# BumpSensors.net
KiCad netlist of a schematic drawn in Altium Designer
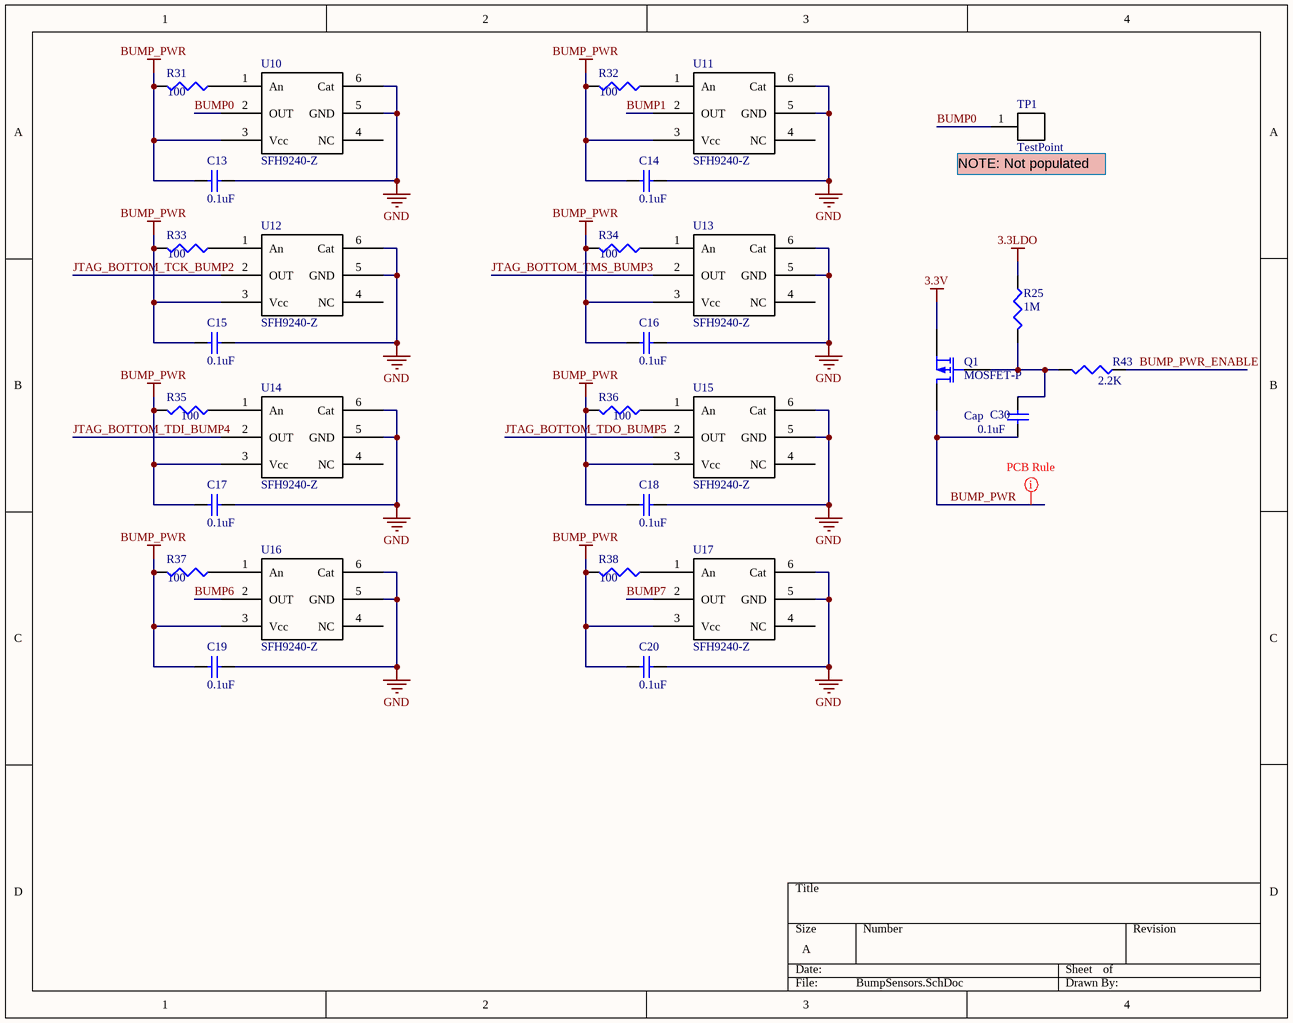
[diagram p0: BumpSensors.SchDoc]

(export (version "E")
  (design (tool "Eeschema 10.0.6"))
  (components
    (comp (ref "C13")
      (value "0.1uF")
      (footprint "CAPC1005L")
      (description "Capacitor (Semiconductor SIM Model)")
      (fields
        (field (name "PART NUMBER") "GRM155R71C104KA88D")
        (field (name "MANUFACTURER") "Murata")
        (field (name "PUBLISHER") "Altium Limited")
      )
      (libsource (lib "Miscellaneous Devices") (part "Cap Semi"))
    )
    (comp (ref "C14")
      (value "0.1uF")
      (footprint "CAPC1005L")
      (description "Capacitor (Semiconductor SIM Model)")
      (fields
        (field (name "PART NUMBER") "GRM155R71C104KA88D")
        (field (name "MANUFACTURER") "Murata")
        (field (name "PUBLISHER") "Altium Limited")
      )
      (libsource (lib "Miscellaneous Devices") (part "Cap Semi"))
    )
    (comp (ref "C15")
      (value "0.1uF")
      (footprint "CAPC1005L")
      (description "Capacitor (Semiconductor SIM Model)")
      (fields
        (field (name "PART NUMBER") "GRM155R71C104KA88D")
        (field (name "MANUFACTURER") "Murata")
        (field (name "PUBLISHER") "Altium Limited")
      )
      (libsource (lib "Miscellaneous Devices") (part "Cap Semi"))
    )
    (comp (ref "C16")
      (value "0.1uF")
      (footprint "CAPC1005L")
      (description "Capacitor (Semiconductor SIM Model)")
      (fields
        (field (name "PART NUMBER") "GRM155R71C104KA88D")
        (field (name "MANUFACTURER") "Murata")
        (field (name "PUBLISHER") "Altium Limited")
      )
      (libsource (lib "Miscellaneous Devices") (part "Cap Semi"))
    )
    (comp (ref "C17")
      (value "0.1uF")
      (footprint "CAPC1005L")
      (description "Capacitor (Semiconductor SIM Model)")
      (fields
        (field (name "PART NUMBER") "GRM155R71C104KA88D")
        (field (name "MANUFACTURER") "Murata")
        (field (name "PUBLISHER") "Altium Limited")
      )
      (libsource (lib "Miscellaneous Devices") (part "Cap Semi"))
    )
    (comp (ref "C18")
      (value "0.1uF")
      (footprint "CAPC1005L")
      (description "Capacitor (Semiconductor SIM Model)")
      (fields
        (field (name "PART NUMBER") "GRM155R71C104KA88D")
        (field (name "MANUFACTURER") "Murata")
        (field (name "PUBLISHER") "Altium Limited")
      )
      (libsource (lib "Miscellaneous Devices") (part "Cap Semi"))
    )
    (comp (ref "C19")
      (value "0.1uF")
      (footprint "CAPC1005L")
      (description "Capacitor (Semiconductor SIM Model)")
      (fields
        (field (name "PART NUMBER") "GRM155R71C104KA88D")
        (field (name "MANUFACTURER") "Murata")
        (field (name "PUBLISHER") "Altium Limited")
      )
      (libsource (lib "Miscellaneous Devices") (part "Cap Semi"))
    )
    (comp (ref "C20")
      (value "0.1uF")
      (footprint "CAPC1005L")
      (description "Capacitor (Semiconductor SIM Model)")
      (fields
        (field (name "PART NUMBER") "GRM155R71C104KA88D")
        (field (name "MANUFACTURER") "Murata")
        (field (name "PUBLISHER") "Altium Limited")
      )
      (libsource (lib "Miscellaneous Devices") (part "Cap Semi"))
    )
    (comp (ref "C30")
      (value "Cap")
      (footprint "CAPC1005L")
      (description "Capacitor")
      (fields
        (field (name "ALTIUM_VALUE") "0.1uF")
        (field (name "PART NUMBER") "GRM155R71C104KA88D")
        (field (name "MANUFACTURER") "Murata")
        (field (name "PUBLISHER") "Altium Limited")
      )
      (libsource (lib "mrone") (part "Cap"))
    )
    (comp (ref "Q1")
      (value "MOSFET-P")
      (footprint "SOT-23")
      (description "P-Channel MOSFET")
      (fields
        (field (name "PART NUMBER") "DMG2301U-7")
        (field (name "MANUFACTURER") "Diodes")
        (field (name "PUBLISHER") "Altium Limited")
      )
      (libsource (lib "mrone") (part "MOSFET-P"))
    )
    (comp (ref "R25")
      (value "1M")
      (footprint "J1-0603")
      (description "Resistor")
      (fields
        (field (name "PART NUMBER") "ERJ-3GEY-J105V")
        (field (name "MANUFACTURER") "Panasonic")
        (field (name "PUBLISHER") "Altium Limited")
      )
      (libsource (lib "Miscellaneous Devices") (part "Res3"))
    )
    (comp (ref "R31")
      (value "100")
      (footprint "RESC1608L")
      (description "Resistor")
      (fields
        (field (name "PART NUMBER") "ERJ-3GEYJ101V")
        (field (name "MANUFACTURER") "Panasonic")
        (field (name "PUBLISHER") "Altium Limited")
      )
      (libsource (lib "Miscellaneous Devices") (part "Res3"))
    )
    (comp (ref "R32")
      (value "100")
      (footprint "RESC1608L")
      (description "Resistor")
      (fields
        (field (name "PART NUMBER") "ERJ-3GEYJ101V")
        (field (name "MANUFACTURER") "Panasonic")
        (field (name "PUBLISHER") "Altium Limited")
      )
      (libsource (lib "Miscellaneous Devices") (part "Res3"))
    )
    (comp (ref "R33")
      (value "100")
      (footprint "RESC1608L")
      (description "Resistor")
      (fields
        (field (name "PART NUMBER") "ERJ-3GEYJ101V")
        (field (name "MANUFACTURER") "Panasonic")
        (field (name "PUBLISHER") "Altium Limited")
      )
      (libsource (lib "Miscellaneous Devices") (part "Res3"))
    )
    (comp (ref "R34")
      (value "100")
      (footprint "RESC1608L")
      (description "Resistor")
      (fields
        (field (name "PART NUMBER") "ERJ-3GEYJ101V")
        (field (name "MANUFACTURER") "Panasonic")
        (field (name "PUBLISHER") "Altium Limited")
      )
      (libsource (lib "Miscellaneous Devices") (part "Res3"))
    )
    (comp (ref "R35")
      (value "100")
      (footprint "RESC1608L")
      (description "Resistor")
      (fields
        (field (name "PART NUMBER") "ERJ-3GEYJ101V")
        (field (name "MANUFACTURER") "Panasonic")
        (field (name "PUBLISHER") "Altium Limited")
      )
      (libsource (lib "Miscellaneous Devices") (part "Res3"))
    )
    (comp (ref "R36")
      (value "100")
      (footprint "RESC1608L")
      (description "Resistor")
      (fields
        (field (name "PART NUMBER") "ERJ-3GEYJ101V")
        (field (name "MANUFACTURER") "Panasonic")
        (field (name "PUBLISHER") "Altium Limited")
      )
      (libsource (lib "Miscellaneous Devices") (part "Res3"))
    )
    (comp (ref "R37")
      (value "100")
      (footprint "RESC1608L")
      (description "Resistor")
      (fields
        (field (name "PART NUMBER") "ERJ-3GEYJ101V")
        (field (name "MANUFACTURER") "Panasonic")
        (field (name "PUBLISHER") "Altium Limited")
      )
      (libsource (lib "Miscellaneous Devices") (part "Res3"))
    )
    (comp (ref "R38")
      (value "100")
      (footprint "RESC1608L")
      (description "Resistor")
      (fields
        (field (name "PART NUMBER") "ERJ-3GEYJ101V")
        (field (name "MANUFACTURER") "Panasonic")
        (field (name "PUBLISHER") "Altium Limited")
      )
      (libsource (lib "Miscellaneous Devices") (part "Res3"))
    )
    (comp (ref "R43")
      (value "2.2K")
      (footprint "J1-0603")
      (description "Resistor")
      (fields
        (field (name "PART NUMBER") "ERJ-3GEYJ222V")
        (field (name "MANUFACTURER") "Panasonic")
        (field (name "PUBLISHER") "Altium Limited")
      )
      (libsource (lib "Miscellaneous Devices") (part "Res3"))
    )
    (comp (ref "TP1")
      (value "TestPoint")
      (footprint "TestPoint")
      (libsource (lib "mrone") (part "TestPoint"))
    )
    (comp (ref "U10")
      (value "SFH9240-Z")
      (footprint "SFH9240-Z")
      (fields (field (name "PART NUMBER") "SFH 9240-Z") (field (name "MANUFACTURER") "OSRAM"))
      (libsource (lib "mrone") (part "SFH9240-Z"))
    )
    (comp (ref "U11")
      (value "SFH9240-Z")
      (footprint "SFH9240-Z")
      (fields (field (name "PART NUMBER") "SFH 9240-Z") (field (name "MANUFACTURER") "OSRAM"))
      (libsource (lib "mrone") (part "SFH9240-Z"))
    )
    (comp (ref "U12")
      (value "SFH9240-Z")
      (footprint "SFH9240-Z")
      (fields (field (name "PART NUMBER") "SFH 9240-Z") (field (name "MANUFACTURER") "OSRAM"))
      (libsource (lib "mrone") (part "SFH9240-Z"))
    )
    (comp (ref "U13")
      (value "SFH9240-Z")
      (footprint "SFH9240-Z")
      (fields (field (name "PART NUMBER") "SFH 9240-Z") (field (name "MANUFACTURER") "OSRAM"))
      (libsource (lib "mrone") (part "SFH9240-Z"))
    )
    (comp (ref "U14")
      (value "SFH9240-Z")
      (footprint "SFH9240-Z")
      (fields (field (name "PART NUMBER") "SFH 9240-Z") (field (name "MANUFACTURER") "OSRAM"))
      (libsource (lib "mrone") (part "SFH9240-Z"))
    )
    (comp (ref "U15")
      (value "SFH9240-Z")
      (footprint "SFH9240-Z")
      (fields (field (name "PART NUMBER") "SFH 9240-Z") (field (name "MANUFACTURER") "OSRAM"))
      (libsource (lib "mrone") (part "SFH9240-Z"))
    )
    (comp (ref "U16")
      (value "SFH9240-Z")
      (footprint "SFH9240-Z")
      (fields (field (name "PART NUMBER") "SFH 9240-Z") (field (name "MANUFACTURER") "OSRAM"))
      (libsource (lib "mrone") (part "SFH9240-Z"))
    )
    (comp (ref "U17")
      (value "SFH9240-Z")
      (footprint "SFH9240-Z")
      (fields (field (name "PART NUMBER") "SFH 9240-Z") (field (name "MANUFACTURER") "OSRAM"))
      (libsource (lib "mrone") (part "SFH9240-Z"))
    )
  )
  (nets
    (net (code "1") (name "/BUMP0") (class "Default")
      (node (ref "TP1") (pin "1") (pintype "passive"))
      (node (ref "U10") (pin "2") (pinfunction "OUT_2") (pintype "passive"))
    )
    (net (code "2") (name "/BUMP1") (class "Default")
      (node (ref "U11") (pin "2") (pinfunction "OUT_2") (pintype "passive"))
    )
    (net (code "3") (name "/BUMP6") (class "Default")
      (node (ref "U16") (pin "2") (pinfunction "OUT_2") (pintype "passive"))
    )
    (net (code "4") (name "/BUMP7") (class "Default")
      (node (ref "U17") (pin "2") (pinfunction "OUT_2") (pintype "passive"))
    )
    (net (code "5") (name "/BUMP_PWR_ENABLE") (class "Default")
      (node (ref "R43") (pin "1") (pinfunction "1_1") (pintype "passive"))
    )
    (net (code "6") (name "/JTAG_BOTTOM_TCK_BUMP2") (class "Default")
      (node (ref "U12") (pin "2") (pinfunction "OUT_2") (pintype "passive"))
    )
    (net (code "7") (name "/JTAG_BOTTOM_TDI_BUMP4") (class "Default")
      (node (ref "U14") (pin "2") (pinfunction "OUT_2") (pintype "passive"))
    )
    (net (code "8") (name "/JTAG_BOTTOM_TDO_BUMP5") (class "Default")
      (node (ref "U15") (pin "2") (pinfunction "OUT_2") (pintype "passive"))
    )
    (net (code "9") (name "/JTAG_BOTTOM_TMS_BUMP3") (class "Default")
      (node (ref "U13") (pin "2") (pinfunction "OUT_2") (pintype "passive"))
    )
    (net (code "10") (name "3.3LDO") (class "Default")
      (node (ref "R25") (pin "1") (pinfunction "1_1") (pintype "passive"))
    )
    (net (code "11") (name "3.3V") (class "Default")
      (node (ref "Q1") (pin "2") (pinfunction "S_2") (pintype "passive"))
    )
    (net (code "12") (name "BUMP_PWR") (class "Default")
      (node (ref "C13") (pin "2") (pinfunction "2_2") (pintype "passive"))
      (node (ref "C14") (pin "2") (pinfunction "2_2") (pintype "passive"))
      (node (ref "C15") (pin "2") (pinfunction "2_2") (pintype "passive"))
      (node (ref "C16") (pin "2") (pinfunction "2_2") (pintype "passive"))
      (node (ref "C17") (pin "2") (pinfunction "2_2") (pintype "passive"))
      (node (ref "C18") (pin "2") (pinfunction "2_2") (pintype "passive"))
      (node (ref "C19") (pin "2") (pinfunction "2_2") (pintype "passive"))
      (node (ref "C20") (pin "2") (pinfunction "2_2") (pintype "passive"))
      (node (ref "C30") (pin "2") (pinfunction "2_2") (pintype "passive"))
      (node (ref "Q1") (pin "3") (pinfunction "D_3") (pintype "passive"))
      (node (ref "R31") (pin "2") (pinfunction "2_2") (pintype "passive"))
      (node (ref "R32") (pin "2") (pinfunction "2_2") (pintype "passive"))
      (node (ref "R33") (pin "2") (pinfunction "2_2") (pintype "passive"))
      (node (ref "R34") (pin "2") (pinfunction "2_2") (pintype "passive"))
      (node (ref "R35") (pin "2") (pinfunction "2_2") (pintype "passive"))
      (node (ref "R36") (pin "2") (pinfunction "2_2") (pintype "passive"))
      (node (ref "R37") (pin "2") (pinfunction "2_2") (pintype "passive"))
      (node (ref "R38") (pin "2") (pinfunction "2_2") (pintype "passive"))
      (node (ref "U10") (pin "3") (pinfunction "Vcc_3") (pintype "passive"))
      (node (ref "U11") (pin "3") (pinfunction "Vcc_3") (pintype "passive"))
      (node (ref "U12") (pin "3") (pinfunction "Vcc_3") (pintype "passive"))
      (node (ref "U13") (pin "3") (pinfunction "Vcc_3") (pintype "passive"))
      (node (ref "U14") (pin "3") (pinfunction "Vcc_3") (pintype "passive"))
      (node (ref "U15") (pin "3") (pinfunction "Vcc_3") (pintype "passive"))
      (node (ref "U16") (pin "3") (pinfunction "Vcc_3") (pintype "passive"))
      (node (ref "U17") (pin "3") (pinfunction "Vcc_3") (pintype "passive"))
    )
    (net (code "13") (name "GND") (class "Default")
      (node (ref "C13") (pin "1") (pinfunction "1_1") (pintype "passive"))
      (node (ref "C14") (pin "1") (pinfunction "1_1") (pintype "passive"))
      (node (ref "C15") (pin "1") (pinfunction "1_1") (pintype "passive"))
      (node (ref "C16") (pin "1") (pinfunction "1_1") (pintype "passive"))
      (node (ref "C17") (pin "1") (pinfunction "1_1") (pintype "passive"))
      (node (ref "C18") (pin "1") (pinfunction "1_1") (pintype "passive"))
      (node (ref "C19") (pin "1") (pinfunction "1_1") (pintype "passive"))
      (node (ref "C20") (pin "1") (pinfunction "1_1") (pintype "passive"))
      (node (ref "U10") (pin "5") (pinfunction "GND_5") (pintype "passive"))
      (node (ref "U10") (pin "6") (pinfunction "Cat_6") (pintype "passive"))
      (node (ref "U11") (pin "5") (pinfunction "GND_5") (pintype "passive"))
      (node (ref "U11") (pin "6") (pinfunction "Cat_6") (pintype "passive"))
      (node (ref "U12") (pin "5") (pinfunction "GND_5") (pintype "passive"))
      (node (ref "U12") (pin "6") (pinfunction "Cat_6") (pintype "passive"))
      (node (ref "U13") (pin "5") (pinfunction "GND_5") (pintype "passive"))
      (node (ref "U13") (pin "6") (pinfunction "Cat_6") (pintype "passive"))
      (node (ref "U14") (pin "5") (pinfunction "GND_5") (pintype "passive"))
      (node (ref "U14") (pin "6") (pinfunction "Cat_6") (pintype "passive"))
      (node (ref "U15") (pin "5") (pinfunction "GND_5") (pintype "passive"))
      (node (ref "U15") (pin "6") (pinfunction "Cat_6") (pintype "passive"))
      (node (ref "U16") (pin "5") (pinfunction "GND_5") (pintype "passive"))
      (node (ref "U16") (pin "6") (pinfunction "Cat_6") (pintype "passive"))
      (node (ref "U17") (pin "5") (pinfunction "GND_5") (pintype "passive"))
      (node (ref "U17") (pin "6") (pinfunction "Cat_6") (pintype "passive"))
    )
    (net (code "14") (name "Net-(Q1-G)") (class "Default")
      (node (ref "C30") (pin "1") (pinfunction "1_1") (pintype "passive"))
      (node (ref "Q1") (pin "1") (pinfunction "G_1") (pintype "passive"))
      (node (ref "R25") (pin "2") (pinfunction "2_2") (pintype "passive"))
      (node (ref "R43") (pin "2") (pinfunction "2_2") (pintype "passive"))
    )
    (net (code "15") (name "Net-(U10-An)") (class "Default")
      (node (ref "R31") (pin "1") (pinfunction "1_1") (pintype "passive"))
      (node (ref "U10") (pin "1") (pinfunction "An_1") (pintype "passive"))
    )
    (net (code "16") (name "Net-(U11-An)") (class "Default")
      (node (ref "R32") (pin "1") (pinfunction "1_1") (pintype "passive"))
      (node (ref "U11") (pin "1") (pinfunction "An_1") (pintype "passive"))
    )
    (net (code "17") (name "Net-(U12-An)") (class "Default")
      (node (ref "R33") (pin "1") (pinfunction "1_1") (pintype "passive"))
      (node (ref "U12") (pin "1") (pinfunction "An_1") (pintype "passive"))
    )
    (net (code "18") (name "Net-(U13-An)") (class "Default")
      (node (ref "R34") (pin "1") (pinfunction "1_1") (pintype "passive"))
      (node (ref "U13") (pin "1") (pinfunction "An_1") (pintype "passive"))
    )
    (net (code "19") (name "Net-(U14-An)") (class "Default")
      (node (ref "R35") (pin "1") (pinfunction "1_1") (pintype "passive"))
      (node (ref "U14") (pin "1") (pinfunction "An_1") (pintype "passive"))
    )
    (net (code "20") (name "Net-(U15-An)") (class "Default")
      (node (ref "R36") (pin "1") (pinfunction "1_1") (pintype "passive"))
      (node (ref "U15") (pin "1") (pinfunction "An_1") (pintype "passive"))
    )
    (net (code "21") (name "Net-(U16-An)") (class "Default")
      (node (ref "R37") (pin "1") (pinfunction "1_1") (pintype "passive"))
      (node (ref "U16") (pin "1") (pinfunction "An_1") (pintype "passive"))
    )
    (net (code "22") (name "Net-(U17-An)") (class "Default")
      (node (ref "R38") (pin "1") (pinfunction "1_1") (pintype "passive"))
      (node (ref "U17") (pin "1") (pinfunction "An_1") (pintype "passive"))
    )
    (net (code "23") (name "unconnected-(U10-NC-Pad4)") (class "Default")
      (node (ref "U10") (pin "4") (pinfunction "NC_4") (pintype "passive"))
    )
    (net (code "24") (name "unconnected-(U11-NC-Pad4)") (class "Default")
      (node (ref "U11") (pin "4") (pinfunction "NC_4") (pintype "passive"))
    )
    (net (code "25") (name "unconnected-(U12-NC-Pad4)") (class "Default")
      (node (ref "U12") (pin "4") (pinfunction "NC_4") (pintype "passive"))
    )
    (net (code "26") (name "unconnected-(U13-NC-Pad4)") (class "Default")
      (node (ref "U13") (pin "4") (pinfunction "NC_4") (pintype "passive"))
    )
    (net (code "27") (name "unconnected-(U14-NC-Pad4)") (class "Default")
      (node (ref "U14") (pin "4") (pinfunction "NC_4") (pintype "passive"))
    )
    (net (code "28") (name "unconnected-(U15-NC-Pad4)") (class "Default")
      (node (ref "U15") (pin "4") (pinfunction "NC_4") (pintype "passive"))
    )
    (net (code "29") (name "unconnected-(U16-NC-Pad4)") (class "Default")
      (node (ref "U16") (pin "4") (pinfunction "NC_4") (pintype "passive"))
    )
    (net (code "30") (name "unconnected-(U17-NC-Pad4)") (class "Default")
      (node (ref "U17") (pin "4") (pinfunction "NC_4") (pintype "passive"))
    )
  )
)
